# car_schematic.net
KiCad netlist of a schematic drawn in Altium Designer
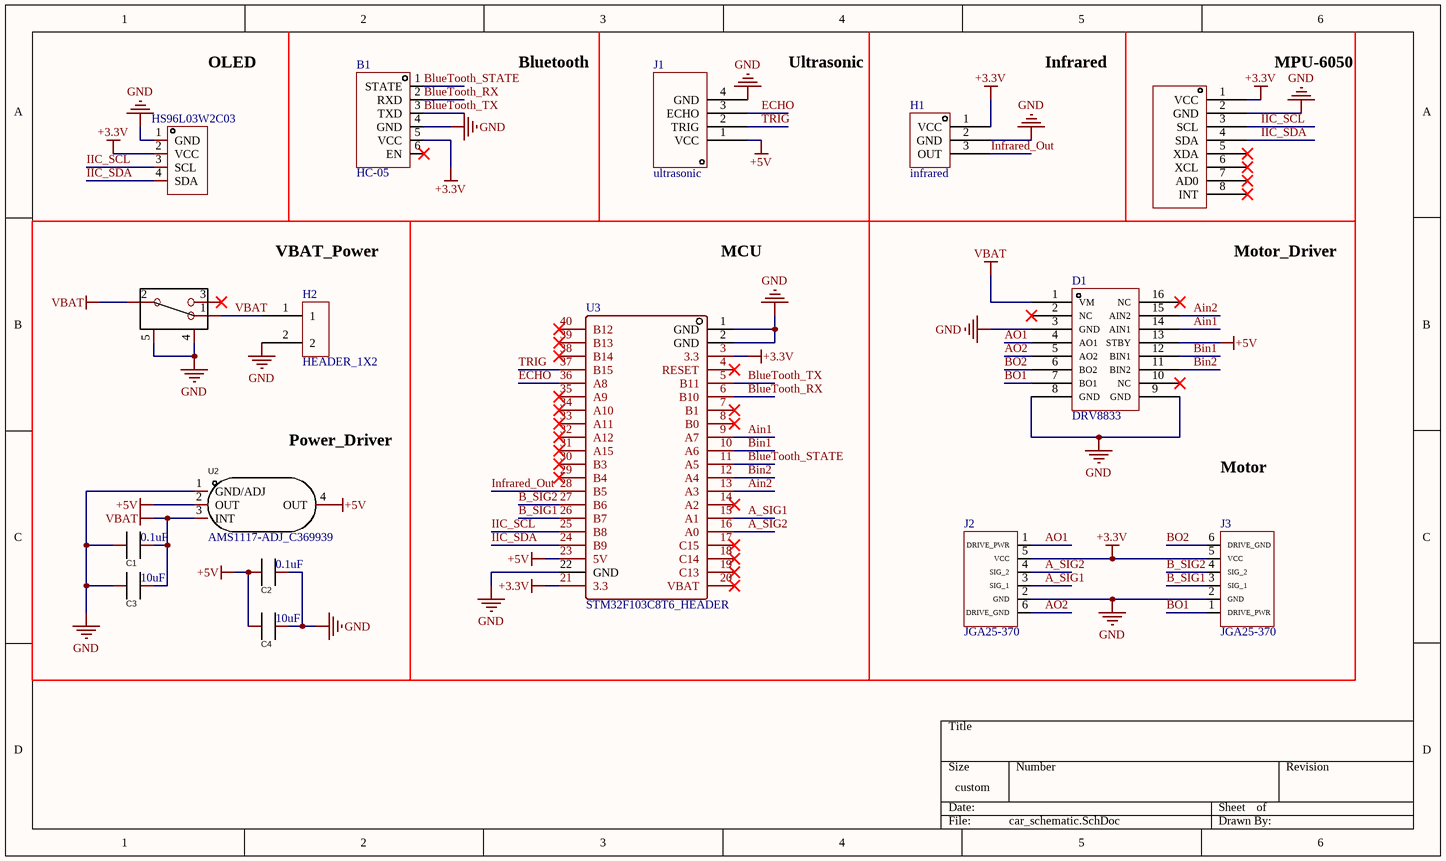
[diagram p0: car_schematic.SchDoc]

(export (version "E")
  (design (tool "Eeschema 10.0.6"))
  (components
    (comp (ref "B1")
      (value "HC-05")
      (footprint "HC-05_HEADER")
      (description "蓝牙模块 VCC接3.3")
      (libsource (lib "car_Schlib") (part "HC-05"))
    )
    (comp (ref "C1")
      (value "0.1uF")
      (footprint "C0603")
      (fields
        (field (name "MANUFACTURER") "SAMSUNG(三星)")
        (field (name "MANUFACTURER PART") "CL10A105KB8NNNC")
        (field (name "TOLERANCE") "±10%")
      )
      (libsource (lib "car_Schlib") (part "C0603"))
    )
    (comp (ref "C2")
      (value "0.1uF")
      (footprint "C0603")
      (fields
        (field (name "MANUFACTURER") "SAMSUNG(三星)")
        (field (name "MANUFACTURER PART") "CL10A105KB8NNNC")
        (field (name "TOLERANCE") "±10%")
      )
      (libsource (lib "car_Schlib") (part "C0603"))
    )
    (comp (ref "C3")
      (value "10uF")
      (footprint "C0603")
      (fields
        (field (name "MANUFACTURER") "SAMSUNG(三星)")
        (field (name "MANUFACTURER PART") "CL10A105KB8NNNC")
        (field (name "TOLERANCE") "±10%")
      )
      (libsource (lib "car_Schlib") (part "C0603"))
    )
    (comp (ref "C4")
      (value "10uF")
      (footprint "C0603")
      (fields
        (field (name "MANUFACTURER") "SAMSUNG(三星)")
        (field (name "MANUFACTURER PART") "CL10A105KB8NNNC")
        (field (name "TOLERANCE") "±10%")
      )
      (libsource (lib "car_Schlib") (part "C0603"))
    )
    (comp (ref "D1")
      (value "DRV8833")
      (footprint "DRV8833_HEADER")
      (description "电机驱动")
      (libsource (lib "car_Schlib") (part "DRV8833"))
    )
    (comp (ref "H1")
      (value "infrared")
      (footprint "RISYM-001_HEADER")
      (description "红外循迹模块")
      (libsource (lib "car_Schlib") (part "RISYM-001"))
    )
    (comp (ref "H2")
      (value "HEADER_1X2")
      (footprint "HEADER_1X2")
      (libsource (lib "car_Schlib") (part "HEADER_1X2"))
    )
    (comp (ref "J1")
      (value "ultrasonic")
      (footprint "HC-SR04_HEADER")
      (description "超声波模块 Pin Header")
      (libsource (lib "car_Schlib") (part "HC-SR04"))
    )
    (comp (ref "J2")
      (value "JGA25-370")
      (footprint "JGA25-370_HEADER")
      (description "JGA25-370 直流减速电机")
      (libsource (lib "") (part "JGA25-370_1"))
    )
    (comp (ref "J3")
      (value "JGA25-370")
      (footprint "JGA25-370_HEADER")
      (description "JGA25-370 直流减速电机")
      (libsource (lib "car_Schlib") (part "JGA25-370"))
    )
    (comp (ref "SW1")
      (value "SS-12F44-G5_C136718")
      (footprint "SW-TH_SS-12F44-GX")
      (description "滑动开关G5")
      (fields (field (name "MANUFACTURER") "韩国韩荣") (field (name "MANUFACTURER PART") "SS-12F44-G5"))
      (libsource (lib "car_Schlib") (part "SS-12F44-G5_C136718"))
    )
    (comp (ref "U1")
      (value "MPU-6050")
      (footprint "MPU-6050_HEADER")
      (description "Pin Header")
      (fields (field (name "MANUFACTURER") "TDK InvenSense(应美盛)"))
      (libsource (lib "car_Schlib") (part "MPU-6050"))
    )
    (comp (ref "U2")
      (value "AMS1117-ADJ_C369939")
      (footprint "SOT-223_L6.5-W3.5-P2.30-LS7.0-BR")
      (description "电源稳压芯片")
      (fields (field (name "MANUFACTURER") "KEXIN(科信)") (field (name "MANUFACTURER PART") "AMS1117-ADJ"))
      (libsource (lib "car_Schlib") (part "AMS1117-ADJ_C369939"))
    )
    (comp (ref "U3")
      (value "STM32F103C8T6_HEADER")
      (footprint "STM32F103C8T6_HEADER")
      (description "Pin Header")
      (libsource (lib "car_Schlib") (part "STM32F103C8T6_HEADER"))
    )
    (comp (ref "U4")
      (value "HS96L03W2C03")
      (footprint "OLED-TH_L27.8-W27.2-P2.54_C9900033791")
      (description "I2C OLED 0.96")
      (fields (field (name "MANUFACTURER") "HS(汉昇)"))
      (libsource (lib "car_Schlib") (part "HS96L03W2C03"))
    )
  )
  (nets
    (net (code "1") (name "+3.3V") (class "Default")
      (node (ref "B1") (pin "5") (pinfunction "VCC_5") (pintype "passive"))
      (node (ref "H1") (pin "1") (pinfunction "VCC_1") (pintype "passive"))
      (node (ref "J2") (pin "5") (pinfunction "VCC_5") (pintype "passive"))
      (node (ref "J3") (pin "5") (pinfunction "VCC_5") (pintype "passive"))
      (node (ref "U1") (pin "1") (pinfunction "VCC_1") (pintype "passive"))
      (node (ref "U3") (pin "21") (pinfunction "3.3_21") (pintype "passive"))
      (node (ref "U3") (pin "3") (pinfunction "3.3_3") (pintype "passive"))
      (node (ref "U4") (pin "2") (pinfunction "VCC_2") (pintype "passive"))
    )
    (net (code "2") (name "+5V") (class "Default")
      (node (ref "C2") (pin "1") (pinfunction "1_1") (pintype "passive"))
      (node (ref "C4") (pin "1") (pinfunction "1_1") (pintype "passive"))
      (node (ref "D1") (pin "13") (pinfunction "STBY_13") (pintype "passive"))
      (node (ref "J1") (pin "1") (pinfunction "VCC_1") (pintype "passive"))
      (node (ref "U2") (pin "2") (pinfunction "OUT_2") (pintype "passive"))
      (node (ref "U2") (pin "4") (pinfunction "OUT_4") (pintype "passive"))
      (node (ref "U3") (pin "23") (pinfunction "5V_23") (pintype "passive"))
    )
    (net (code "3") (name "/AO1") (class "Default")
      (node (ref "D1") (pin "4") (pinfunction "AO1_4") (pintype "passive"))
      (node (ref "J2") (pin "1") (pinfunction "DRIVE_PWR_1") (pintype "passive"))
    )
    (net (code "4") (name "/AO2") (class "Default")
      (node (ref "D1") (pin "5") (pinfunction "AO2_5") (pintype "passive"))
      (node (ref "J2") (pin "6") (pinfunction "DRIVE_GND_6") (pintype "passive"))
    )
    (net (code "5") (name "/A_SIG1") (class "Default")
      (node (ref "J2") (pin "3") (pinfunction "SIG_1_3") (pintype "passive"))
      (node (ref "U3") (pin "15") (pinfunction "A1_15") (pintype "passive"))
    )
    (net (code "6") (name "/A_SIG2") (class "Default")
      (node (ref "J2") (pin "4") (pinfunction "SIG_2_4") (pintype "passive"))
      (node (ref "U3") (pin "16") (pinfunction "A0_16") (pintype "passive"))
    )
    (net (code "7") (name "/Ain1") (class "Default")
      (node (ref "D1") (pin "14") (pinfunction "AIN1_14") (pintype "passive"))
      (node (ref "U3") (pin "9") (pinfunction "A7_9") (pintype "passive"))
    )
    (net (code "8") (name "/Ain2") (class "Default")
      (node (ref "D1") (pin "15") (pinfunction "AIN2_15") (pintype "passive"))
      (node (ref "U3") (pin "13") (pinfunction "A3_13") (pintype "passive"))
    )
    (net (code "9") (name "/BO1") (class "Default")
      (node (ref "D1") (pin "7") (pinfunction "BO1_7") (pintype "passive"))
      (node (ref "J3") (pin "1") (pinfunction "DRIVE_PWR_1") (pintype "passive"))
    )
    (net (code "10") (name "/BO2") (class "Default")
      (node (ref "D1") (pin "6") (pinfunction "BO2_6") (pintype "passive"))
      (node (ref "J3") (pin "6") (pinfunction "DRIVE_GND_6") (pintype "passive"))
    )
    (net (code "11") (name "/B_SIG1") (class "Default")
      (node (ref "J3") (pin "3") (pinfunction "SIG_1_3") (pintype "passive"))
      (node (ref "U3") (pin "26") (pinfunction "B7_26") (pintype "passive"))
    )
    (net (code "12") (name "/B_SIG2") (class "Default")
      (node (ref "J3") (pin "4") (pinfunction "SIG_2_4") (pintype "passive"))
      (node (ref "U3") (pin "27") (pinfunction "B6_27") (pintype "passive"))
    )
    (net (code "13") (name "/Bin1") (class "Default")
      (node (ref "D1") (pin "12") (pinfunction "BIN1_12") (pintype "passive"))
      (node (ref "U3") (pin "10") (pinfunction "A6_10") (pintype "passive"))
    )
    (net (code "14") (name "/Bin2") (class "Default")
      (node (ref "D1") (pin "11") (pinfunction "BIN2_11") (pintype "passive"))
      (node (ref "U3") (pin "12") (pinfunction "A4_12") (pintype "passive"))
    )
    (net (code "15") (name "/BlueTooth_RX") (class "Default")
      (node (ref "B1") (pin "2") (pinfunction "RXD_2") (pintype "passive"))
      (node (ref "U3") (pin "6") (pinfunction "B10_6") (pintype "passive"))
    )
    (net (code "16") (name "/BlueTooth_STATE") (class "Default")
      (node (ref "B1") (pin "1") (pinfunction "STATE_1") (pintype "passive"))
      (node (ref "U3") (pin "11") (pinfunction "A5_11") (pintype "passive"))
    )
    (net (code "17") (name "/BlueTooth_TX") (class "Default")
      (node (ref "B1") (pin "3") (pinfunction "TXD_3") (pintype "passive"))
      (node (ref "U3") (pin "5") (pinfunction "B11_5") (pintype "passive"))
    )
    (net (code "18") (name "/ECHO") (class "Default")
      (node (ref "J1") (pin "3") (pinfunction "ECHO_3") (pintype "passive"))
      (node (ref "U3") (pin "36") (pinfunction "A8_36") (pintype "passive"))
    )
    (net (code "19") (name "/IIC_SCL") (class "Default")
      (node (ref "U1") (pin "3") (pinfunction "SCL_3") (pintype "passive"))
      (node (ref "U3") (pin "25") (pinfunction "B8_25") (pintype "passive"))
      (node (ref "U4") (pin "3") (pinfunction "SCL_3") (pintype "passive"))
    )
    (net (code "20") (name "/IIC_SDA") (class "Default")
      (node (ref "U1") (pin "4") (pinfunction "SDA_4") (pintype "passive"))
      (node (ref "U3") (pin "24") (pinfunction "B9_24") (pintype "passive"))
      (node (ref "U4") (pin "4") (pinfunction "SDA_4") (pintype "passive"))
    )
    (net (code "21") (name "/Infrared_Out") (class "Default")
      (node (ref "H1") (pin "3") (pinfunction "OUT_3") (pintype "passive"))
      (node (ref "U3") (pin "28") (pinfunction "B5_28") (pintype "passive"))
    )
    (net (code "22") (name "/TRIG") (class "Default")
      (node (ref "J1") (pin "2") (pinfunction "TRIG_2") (pintype "passive"))
      (node (ref "U3") (pin "37") (pinfunction "B15_37") (pintype "passive"))
    )
    (net (code "23") (name "GND") (class "Default")
      (node (ref "B1") (pin "4") (pinfunction "GND_4") (pintype "passive"))
      (node (ref "C1") (pin "1") (pinfunction "1_1") (pintype "passive"))
      (node (ref "C2") (pin "2") (pinfunction "2_2") (pintype "passive"))
      (node (ref "C3") (pin "1") (pinfunction "1_1") (pintype "passive"))
      (node (ref "C4") (pin "2") (pinfunction "2_2") (pintype "passive"))
      (node (ref "D1") (pin "3") (pinfunction "GND_3") (pintype "passive"))
      (node (ref "D1") (pin "8") (pinfunction "GND_8") (pintype "passive"))
      (node (ref "D1") (pin "9") (pinfunction "GND_9") (pintype "passive"))
      (node (ref "H1") (pin "2") (pinfunction "GND_2") (pintype "passive"))
      (node (ref "H2") (pin "2") (pinfunction "2_2") (pintype "passive"))
      (node (ref "J1") (pin "4") (pinfunction "GND_4") (pintype "passive"))
      (node (ref "J2") (pin "2") (pinfunction "GND_2") (pintype "passive"))
      (node (ref "J3") (pin "2") (pinfunction "GND_2") (pintype "passive"))
      (node (ref "SW1") (pin "4") (pinfunction "4_4") (pintype "passive"))
      (node (ref "SW1") (pin "5") (pinfunction "5_5") (pintype "passive"))
      (node (ref "U1") (pin "2") (pinfunction "GND_2") (pintype "passive"))
      (node (ref "U2") (pin "1") (pinfunction "GND/ADJ_1") (pintype "passive"))
      (node (ref "U3") (pin "1") (pinfunction "GND_1") (pintype "passive"))
      (node (ref "U3") (pin "2") (pinfunction "GND_2") (pintype "passive"))
      (node (ref "U3") (pin "22") (pinfunction "GND_22") (pintype "passive"))
      (node (ref "U4") (pin "1") (pinfunction "GND_1") (pintype "passive"))
    )
    (net (code "24") (name "VBAT") (class "Default")
      (node (ref "C1") (pin "2") (pinfunction "2_2") (pintype "passive"))
      (node (ref "C3") (pin "2") (pinfunction "2_2") (pintype "passive"))
      (node (ref "D1") (pin "1") (pinfunction "VM_1") (pintype "passive"))
      (node (ref "H2") (pin "1") (pinfunction "1_1") (pintype "passive"))
      (node (ref "SW1") (pin "1") (pinfunction "1_1") (pintype "passive"))
      (node (ref "SW1") (pin "2") (pinfunction "2_2") (pintype "passive"))
      (node (ref "U2") (pin "3") (pinfunction "INT_3") (pintype "passive"))
    )
    (net (code "25") (name "unconnected-(B1-EN-Pad6)") (class "Default")
      (node (ref "B1") (pin "6") (pinfunction "EN_6") (pintype "passive+no_connect"))
    )
    (net (code "26") (name "unconnected-(D1-NC-Pad2)") (class "Default")
      (node (ref "D1") (pin "2") (pinfunction "NC_2") (pintype "passive+no_connect"))
    )
    (net (code "27") (name "unconnected-(D1-NC-Pad10)") (class "Default")
      (node (ref "D1") (pin "10") (pinfunction "NC_10") (pintype "passive+no_connect"))
    )
    (net (code "28") (name "unconnected-(D1-NC-Pad16)") (class "Default")
      (node (ref "D1") (pin "16") (pinfunction "NC_16") (pintype "passive+no_connect"))
    )
    (net (code "29") (name "unconnected-(SW1-Pad3)") (class "Default")
      (node (ref "SW1") (pin "3") (pinfunction "3_3") (pintype "passive+no_connect"))
    )
    (net (code "30") (name "unconnected-(U1-AD0-Pad7)") (class "Default")
      (node (ref "U1") (pin "7") (pinfunction "AD0_7") (pintype "passive+no_connect"))
    )
    (net (code "31") (name "unconnected-(U1-INT-Pad8)") (class "Default")
      (node (ref "U1") (pin "8") (pinfunction "INT_8") (pintype "passive+no_connect"))
    )
    (net (code "32") (name "unconnected-(U1-XCL-Pad6)") (class "Default")
      (node (ref "U1") (pin "6") (pinfunction "XCL_6") (pintype "passive+no_connect"))
    )
    (net (code "33") (name "unconnected-(U1-XDA-Pad5)") (class "Default")
      (node (ref "U1") (pin "5") (pinfunction "XDA_5") (pintype "passive+no_connect"))
    )
    (net (code "34") (name "unconnected-(U3-A2-Pad14)") (class "Default")
      (node (ref "U3") (pin "14") (pinfunction "A2_14") (pintype "passive+no_connect"))
    )
    (net (code "35") (name "unconnected-(U3-A9-Pad35)") (class "Default")
      (node (ref "U3") (pin "35") (pinfunction "A9_35") (pintype "passive+no_connect"))
    )
    (net (code "36") (name "unconnected-(U3-A10-Pad34)") (class "Default")
      (node (ref "U3") (pin "34") (pinfunction "A10_34") (pintype "passive+no_connect"))
    )
    (net (code "37") (name "unconnected-(U3-A11-Pad33)") (class "Default")
      (node (ref "U3") (pin "33") (pinfunction "A11_33") (pintype "passive+no_connect"))
    )
    (net (code "38") (name "unconnected-(U3-A12-Pad32)") (class "Default")
      (node (ref "U3") (pin "32") (pinfunction "A12_32") (pintype "passive+no_connect"))
    )
    (net (code "39") (name "unconnected-(U3-A15-Pad31)") (class "Default")
      (node (ref "U3") (pin "31") (pinfunction "A15_31") (pintype "passive+no_connect"))
    )
    (net (code "40") (name "unconnected-(U3-B0-Pad8)") (class "Default")
      (node (ref "U3") (pin "8") (pinfunction "B0_8") (pintype "passive+no_connect"))
    )
    (net (code "41") (name "unconnected-(U3-B1-Pad7)") (class "Default")
      (node (ref "U3") (pin "7") (pinfunction "B1_7") (pintype "passive+no_connect"))
    )
    (net (code "42") (name "unconnected-(U3-B3-Pad30)") (class "Default")
      (node (ref "U3") (pin "30") (pinfunction "B3_30") (pintype "passive+no_connect"))
    )
    (net (code "43") (name "unconnected-(U3-B4-Pad29)") (class "Default")
      (node (ref "U3") (pin "29") (pinfunction "B4_29") (pintype "passive+no_connect"))
    )
    (net (code "44") (name "unconnected-(U3-B12-Pad40)") (class "Default")
      (node (ref "U3") (pin "40") (pinfunction "B12_40") (pintype "passive+no_connect"))
    )
    (net (code "45") (name "unconnected-(U3-B13-Pad39)") (class "Default")
      (node (ref "U3") (pin "39") (pinfunction "B13_39") (pintype "passive+no_connect"))
    )
    (net (code "46") (name "unconnected-(U3-B14-Pad38)") (class "Default")
      (node (ref "U3") (pin "38") (pinfunction "B14_38") (pintype "passive+no_connect"))
    )
    (net (code "47") (name "unconnected-(U3-C13-Pad19)") (class "Default")
      (node (ref "U3") (pin "19") (pinfunction "C13_19") (pintype "passive+no_connect"))
    )
    (net (code "48") (name "unconnected-(U3-C14-Pad18)") (class "Default")
      (node (ref "U3") (pin "18") (pinfunction "C14_18") (pintype "passive+no_connect"))
    )
    (net (code "49") (name "unconnected-(U3-C15-Pad17)") (class "Default")
      (node (ref "U3") (pin "17") (pinfunction "C15_17") (pintype "passive+no_connect"))
    )
    (net (code "50") (name "unconnected-(U3-RESET-Pad4)") (class "Default")
      (node (ref "U3") (pin "4") (pinfunction "RESET_4") (pintype "passive+no_connect"))
    )
    (net (code "51") (name "unconnected-(U3-VBAT-Pad20)") (class "Default")
      (node (ref "U3") (pin "20") (pinfunction "VBAT_20") (pintype "passive+no_connect"))
    )
  )
)
